# Battery.net
KiCad netlist of a schematic drawn in EAGLE
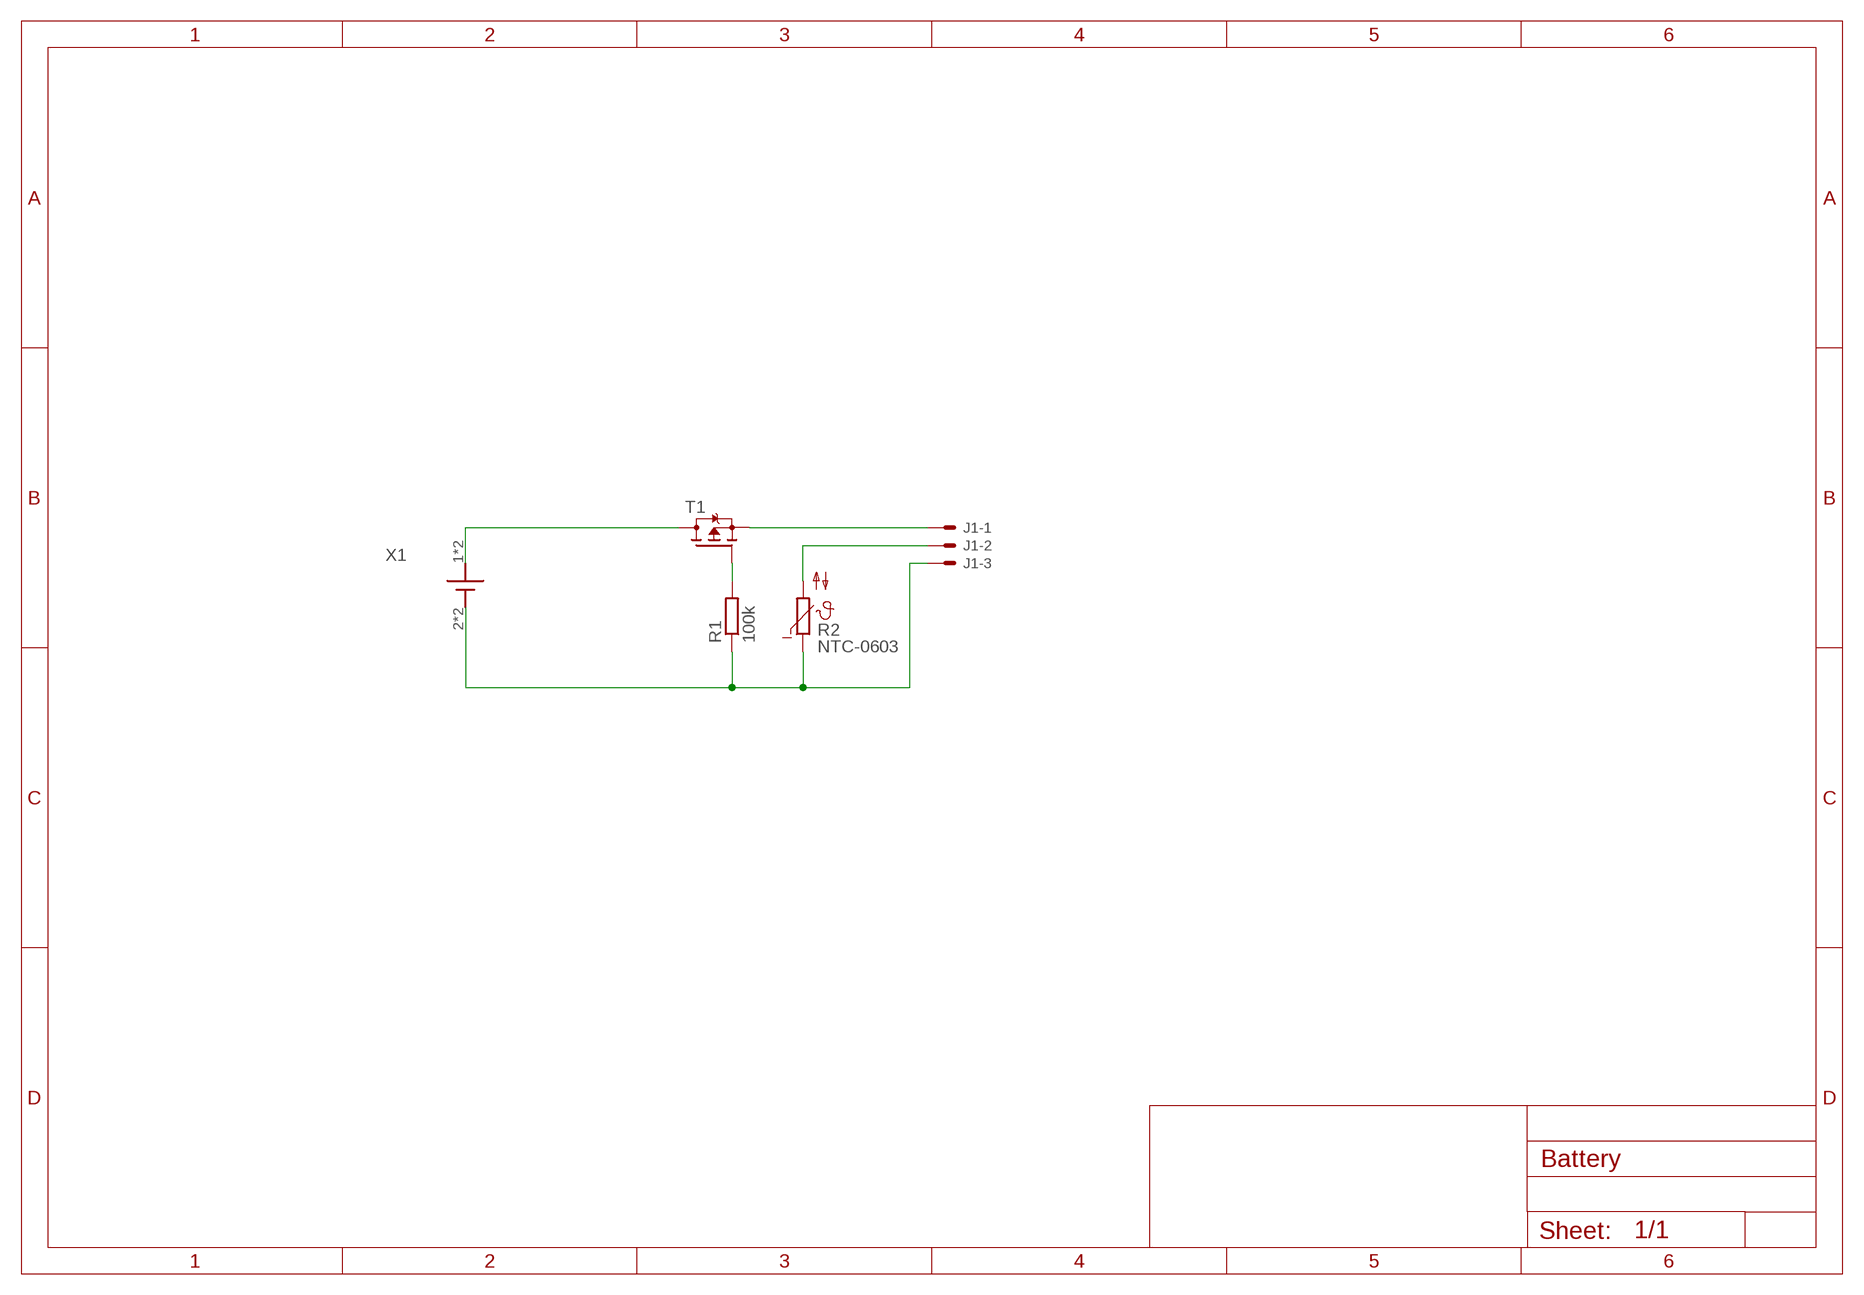
[diagram p0: schematic, sheet 1]

(export (version "E")
  (design (tool "Eeschema 10.0.6"))
  (components
    (comp (ref "J1")
      (value "22-05-7038-03")
      (footprint "eagle-import:7395-03")
      (fields (field (name "OC_MOUSER") "538-22-05-7038"))
      (libsource (lib "eagle-import") (part "22-?-0305-7038"))
    )
    (comp (ref "R1")
      (value "100k")
      (footprint "eagle-import:R0603")
      (libsource (lib "eagle-import") (part "R-EU_R0603"))
    )
    (comp (ref "R2")
      (value "NTC-0603")
      (footprint "eagle-import:R0603")
      (libsource (lib "eagle-import") (part "NTC-0603"))
    )
    (comp (ref "T1")
      (value "PMOS")
      (footprint "eagle-import:SOT23")
      (libsource (lib "eagle-import") (part "PMOS"))
    )
    (comp (ref "X1")
      (value "LI-ION_BATHOL2")
      (footprint "eagle-import:HOLDER_2")
      (libsource (lib "eagle-import") (part "LI-ION_BATHOL2"))
    )
  )
  (nets
    (net (code "1") (name "Net-(J1A-S)") (class "Default")
      (node (ref "J1") (pin "1") (pinfunction "S_1") (pintype "passive"))
      (node (ref "T1") (pin "2") (pinfunction "S_2") (pintype "passive"))
    )
    (net (code "2") (name "Net-(J1B-S)") (class "Default")
      (node (ref "J1") (pin "2") (pinfunction "S_2") (pintype "passive"))
      (node (ref "R2") (pin "2") (pinfunction "2_2") (pintype "passive"))
    )
    (net (code "3") (name "Net-(J1C-S)") (class "Default")
      (node (ref "J1") (pin "3") (pinfunction "S_3") (pintype "passive"))
      (node (ref "R1") (pin "1") (pinfunction "1_1") (pintype "passive"))
      (node (ref "R2") (pin "1") (pinfunction "1_1") (pintype "passive"))
      (node (ref "X1") (pin "2") (pinfunction "VBAT-1_2") (pintype "passive"))
      (node (ref "X1") (pin "3") (pinfunction "VBAT-1_3") (pintype "passive"))
    )
    (net (code "4") (name "Net-(T1-D)") (class "Default")
      (node (ref "T1") (pin "3") (pinfunction "D_3") (pintype "passive"))
      (node (ref "X1") (pin "1") (pinfunction "VBAT+1_1") (pintype "passive"))
      (node (ref "X1") (pin "4") (pinfunction "VBAT+1_4") (pintype "passive"))
    )
    (net (code "5") (name "Net-(T1-G)") (class "Default")
      (node (ref "R1") (pin "2") (pinfunction "2_2") (pintype "passive"))
      (node (ref "T1") (pin "1") (pinfunction "G_1") (pintype "passive"))
    )
  )
)
